# Sheet1.net
KiCad netlist of a schematic drawn in Altium Designer
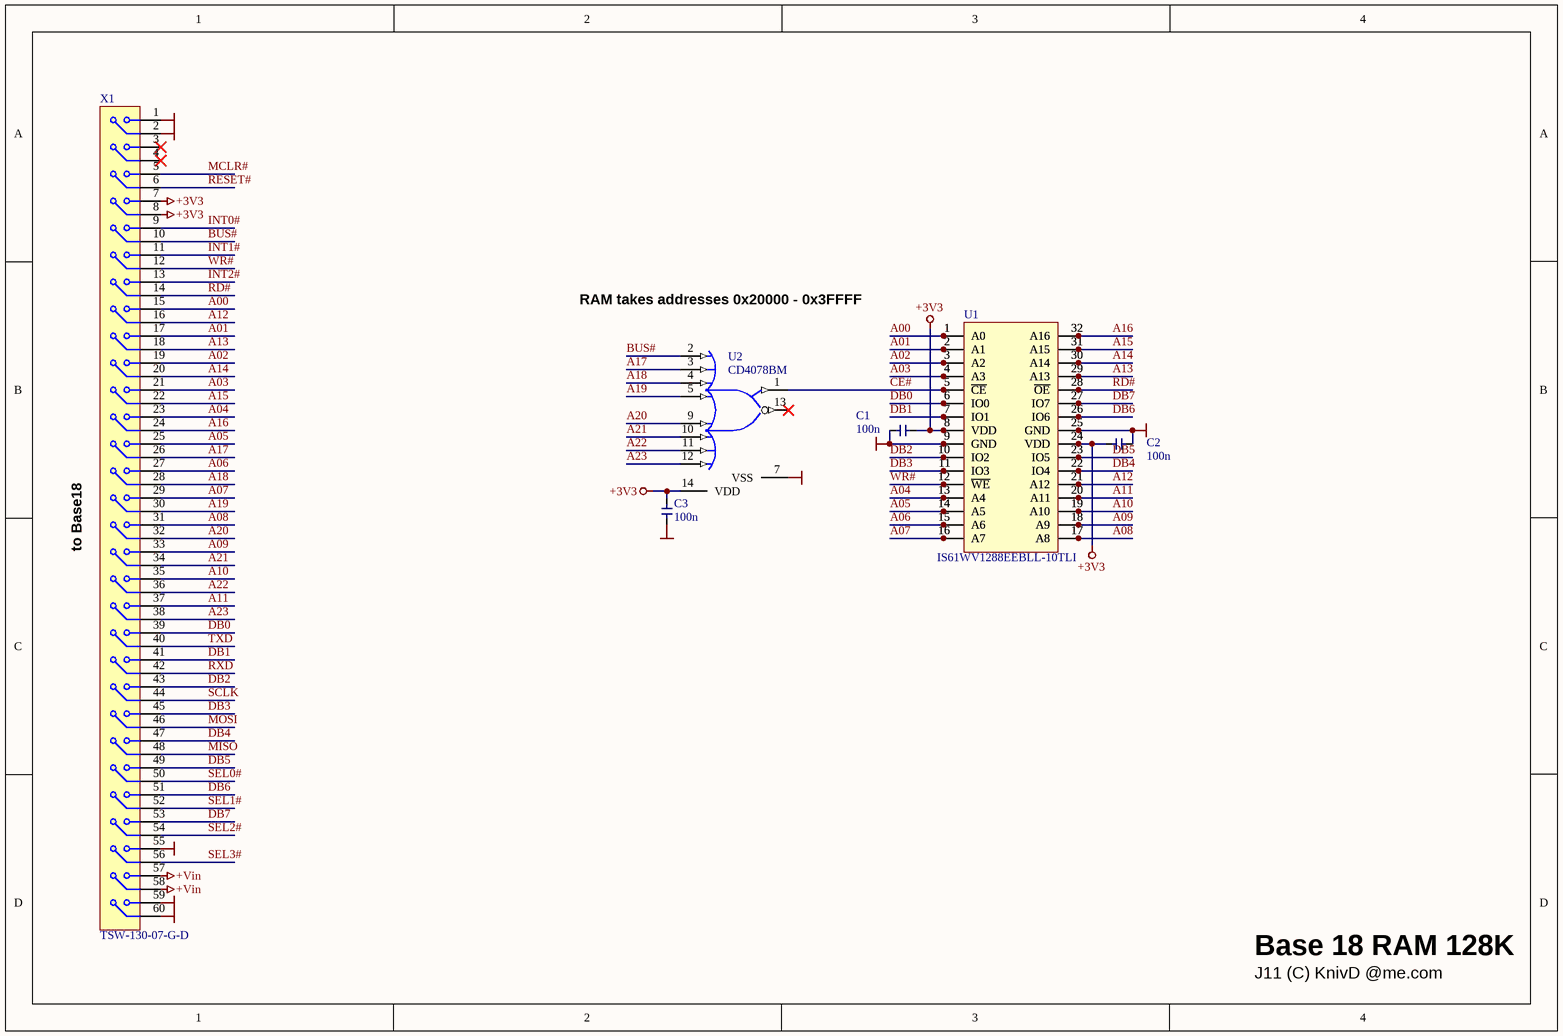
[diagram p0: Sheet1.SchDoc]

(export (version "E")
  (design (tool "Eeschema 10.0.6"))
  (components
    (comp (ref "C1")
      (value "100n")
      (footprint "CAPC3216X110N")
      (description "Capacitor")
      (libsource (lib "Discretes") (part "Capacitor"))
    )
    (comp (ref "C2")
      (value "100n")
      (footprint "CAPC3216X110N")
      (description "Capacitor")
      (libsource (lib "Discretes") (part "Capacitor"))
    )
    (comp (ref "C3")
      (value "100n")
      (footprint "CAPC3216X110N")
      (description "Capacitor")
      (libsource (lib "Discretes") (part "Capacitor"))
    )
    (comp (ref "U1")
      (value "IS61WV1288EEBLL-10TLI")
      (footprint "SOIC127P1413X280-32N")
      (description "128k x8 high-speed CMOS static RAM 3.3V")
      (fields (field (name "MANUFACTURER") "ISSI"))
      (libsource (lib "IC Other Functions") (part "IS63LV1024L"))
    )
    (comp (ref "U1A")
      (value "~")
      (footprint "SOJ127P1118X368-32N")
      (description "128k x8 high-speed CMOS static RAM 3.3V")
      (libsource (lib "IC Other Functions") (part "IS63LV1024L"))
    )
    (comp (ref "U2")
      (value "CD4078BM")
      (footprint "SOIC127P600X175-14N")
      (description "8-Input NOR Gate")
      (fields
        (field (name "PART NUMBER") "CD4078BE")
        (field (name "MANUFACTURER") "TEXAS INSTRUMENTS")
        (field (name "AUTHOR") "CERN DEM JLC")
      )
      (libsource (lib "ICs And Semiconductors") (part "4078"))
    )
    (comp (ref "X1")
      (value "TSW-130-07-G-D")
      (footprint "DIL60-M-EDGE")
      (description "Dual row, 60-way connector")
      (libsource (lib "Connectors") (part "Connector 2x30"))
    )
  )
  (nets
    (net (code "1") (name "+3V3") (class "Default")
      (node (ref "C1") (pin "1") (pintype "passive"))
      (node (ref "C2") (pin "1") (pintype "passive"))
      (node (ref "C3") (pin "1") (pintype "passive"))
      (node (ref "U1") (pin "24") (pinfunction "VDD_24") (pintype "passive"))
      (node (ref "U1") (pin "8") (pinfunction "VDD_8") (pintype "passive"))
      (node (ref "U1A") (pin "24") (pinfunction "VDD_24") (pintype "passive"))
      (node (ref "U1A") (pin "8") (pinfunction "VDD_8") (pintype "passive"))
      (node (ref "U2") (pin "14") (pinfunction "VDD_14") (pintype "power_in"))
      (node (ref "X1") (pin "7") (pinfunction "7_7") (pintype "passive"))
      (node (ref "X1") (pin "8") (pinfunction "8_8") (pintype "passive"))
    )
    (net (code "2") (name "+Vin") (class "Default")
      (node (ref "X1") (pin "57") (pinfunction "57_57") (pintype "passive"))
      (node (ref "X1") (pin "58") (pinfunction "58_58") (pintype "passive"))
    )
    (net (code "3") (name "/A00") (class "Default")
      (node (ref "U1") (pin "1") (pinfunction "A0_1") (pintype "passive"))
      (node (ref "U1A") (pin "1") (pinfunction "A0_1") (pintype "passive"))
      (node (ref "X1") (pin "15") (pinfunction "15_15") (pintype "passive"))
    )
    (net (code "4") (name "/A01") (class "Default")
      (node (ref "U1") (pin "2") (pinfunction "A1_2") (pintype "passive"))
      (node (ref "U1A") (pin "2") (pinfunction "A1_2") (pintype "passive"))
      (node (ref "X1") (pin "17") (pinfunction "17_17") (pintype "passive"))
    )
    (net (code "5") (name "/A02") (class "Default")
      (node (ref "U1") (pin "3") (pinfunction "A2_3") (pintype "passive"))
      (node (ref "U1A") (pin "3") (pinfunction "A2_3") (pintype "passive"))
      (node (ref "X1") (pin "19") (pinfunction "19_19") (pintype "passive"))
    )
    (net (code "6") (name "/A03") (class "Default")
      (node (ref "U1") (pin "4") (pinfunction "A3_4") (pintype "passive"))
      (node (ref "U1A") (pin "4") (pinfunction "A3_4") (pintype "passive"))
      (node (ref "X1") (pin "21") (pinfunction "21_21") (pintype "passive"))
    )
    (net (code "7") (name "/A04") (class "Default")
      (node (ref "U1") (pin "13") (pinfunction "A4_13") (pintype "passive"))
      (node (ref "U1A") (pin "13") (pinfunction "A4_13") (pintype "passive"))
      (node (ref "X1") (pin "23") (pinfunction "23_23") (pintype "passive"))
    )
    (net (code "8") (name "/A05") (class "Default")
      (node (ref "U1") (pin "14") (pinfunction "A5_14") (pintype "passive"))
      (node (ref "U1A") (pin "14") (pinfunction "A5_14") (pintype "passive"))
      (node (ref "X1") (pin "25") (pinfunction "25_25") (pintype "passive"))
    )
    (net (code "9") (name "/A06") (class "Default")
      (node (ref "U1") (pin "15") (pinfunction "A6_15") (pintype "passive"))
      (node (ref "U1A") (pin "15") (pinfunction "A6_15") (pintype "passive"))
      (node (ref "X1") (pin "27") (pinfunction "27_27") (pintype "passive"))
    )
    (net (code "10") (name "/A07") (class "Default")
      (node (ref "U1") (pin "16") (pinfunction "A7_16") (pintype "passive"))
      (node (ref "U1A") (pin "16") (pinfunction "A7_16") (pintype "passive"))
      (node (ref "X1") (pin "29") (pinfunction "29_29") (pintype "passive"))
    )
    (net (code "11") (name "/A08") (class "Default")
      (node (ref "U1") (pin "17") (pinfunction "A8_17") (pintype "passive"))
      (node (ref "U1A") (pin "17") (pinfunction "A8_17") (pintype "passive"))
      (node (ref "X1") (pin "31") (pinfunction "31_31") (pintype "passive"))
    )
    (net (code "12") (name "/A09") (class "Default")
      (node (ref "U1") (pin "18") (pinfunction "A9_18") (pintype "passive"))
      (node (ref "U1A") (pin "18") (pinfunction "A9_18") (pintype "passive"))
      (node (ref "X1") (pin "33") (pinfunction "33_33") (pintype "passive"))
    )
    (net (code "13") (name "/A10") (class "Default")
      (node (ref "U1") (pin "19") (pinfunction "A10_19") (pintype "passive"))
      (node (ref "U1A") (pin "19") (pinfunction "A10_19") (pintype "passive"))
      (node (ref "X1") (pin "35") (pinfunction "35_35") (pintype "passive"))
    )
    (net (code "14") (name "/A11") (class "Default")
      (node (ref "U1") (pin "20") (pinfunction "A11_20") (pintype "passive"))
      (node (ref "U1A") (pin "20") (pinfunction "A11_20") (pintype "passive"))
      (node (ref "X1") (pin "37") (pinfunction "37_37") (pintype "passive"))
    )
    (net (code "15") (name "/A12") (class "Default")
      (node (ref "U1") (pin "21") (pinfunction "A12_21") (pintype "passive"))
      (node (ref "U1A") (pin "21") (pinfunction "A12_21") (pintype "passive"))
      (node (ref "X1") (pin "16") (pinfunction "16_16") (pintype "passive"))
    )
    (net (code "16") (name "/A13") (class "Default")
      (node (ref "U1") (pin "29") (pinfunction "A13_29") (pintype "passive"))
      (node (ref "U1A") (pin "29") (pinfunction "A13_29") (pintype "passive"))
      (node (ref "X1") (pin "18") (pinfunction "18_18") (pintype "passive"))
    )
    (net (code "17") (name "/A14") (class "Default")
      (node (ref "U1") (pin "30") (pinfunction "A14_30") (pintype "passive"))
      (node (ref "U1A") (pin "30") (pinfunction "A14_30") (pintype "passive"))
      (node (ref "X1") (pin "20") (pinfunction "20_20") (pintype "passive"))
    )
    (net (code "18") (name "/A15") (class "Default")
      (node (ref "U1") (pin "31") (pinfunction "A15_31") (pintype "passive"))
      (node (ref "U1A") (pin "31") (pinfunction "A15_31") (pintype "passive"))
      (node (ref "X1") (pin "22") (pinfunction "22_22") (pintype "passive"))
    )
    (net (code "19") (name "/A16") (class "Default")
      (node (ref "U1") (pin "32") (pinfunction "A16_32") (pintype "passive"))
      (node (ref "U1A") (pin "32") (pinfunction "A16_32") (pintype "passive"))
      (node (ref "X1") (pin "24") (pinfunction "24_24") (pintype "passive"))
    )
    (net (code "20") (name "/A17") (class "Default")
      (node (ref "U2") (pin "3") (pintype "input"))
      (node (ref "X1") (pin "26") (pinfunction "26_26") (pintype "passive"))
    )
    (net (code "21") (name "/A18") (class "Default")
      (node (ref "U2") (pin "4") (pintype "input"))
      (node (ref "X1") (pin "28") (pinfunction "28_28") (pintype "passive"))
    )
    (net (code "22") (name "/A19") (class "Default")
      (node (ref "U2") (pin "5") (pintype "input"))
      (node (ref "X1") (pin "30") (pinfunction "30_30") (pintype "passive"))
    )
    (net (code "23") (name "/A20") (class "Default")
      (node (ref "U2") (pin "9") (pintype "input"))
      (node (ref "X1") (pin "32") (pinfunction "32_32") (pintype "passive"))
    )
    (net (code "24") (name "/A21") (class "Default")
      (node (ref "U2") (pin "10") (pintype "input"))
      (node (ref "X1") (pin "34") (pinfunction "34_34") (pintype "passive"))
    )
    (net (code "25") (name "/A22") (class "Default")
      (node (ref "U2") (pin "11") (pintype "input"))
      (node (ref "X1") (pin "36") (pinfunction "36_36") (pintype "passive"))
    )
    (net (code "26") (name "/A23") (class "Default")
      (node (ref "U2") (pin "12") (pintype "input"))
      (node (ref "X1") (pin "38") (pinfunction "38_38") (pintype "passive"))
    )
    (net (code "27") (name "/BUS#") (class "Default")
      (node (ref "U2") (pin "2") (pintype "input"))
      (node (ref "X1") (pin "10") (pinfunction "10_10") (pintype "passive"))
    )
    (net (code "28") (name "/CE#") (class "Default")
      (node (ref "U1") (pin "5") (pinfunction "~{CE}_5") (pintype "passive"))
      (node (ref "U1A") (pin "5") (pinfunction "~{CE}_5") (pintype "passive"))
      (node (ref "U2") (pin "1") (pintype "output"))
    )
    (net (code "29") (name "/DB0") (class "Default")
      (node (ref "U1") (pin "6") (pinfunction "IO0_6") (pintype "passive"))
      (node (ref "U1A") (pin "6") (pinfunction "IO0_6") (pintype "passive"))
      (node (ref "X1") (pin "39") (pinfunction "39_39") (pintype "passive"))
    )
    (net (code "30") (name "/DB1") (class "Default")
      (node (ref "U1") (pin "7") (pinfunction "IO1_7") (pintype "passive"))
      (node (ref "U1A") (pin "7") (pinfunction "IO1_7") (pintype "passive"))
      (node (ref "X1") (pin "41") (pinfunction "41_41") (pintype "passive"))
    )
    (net (code "31") (name "/DB2") (class "Default")
      (node (ref "U1") (pin "10") (pinfunction "IO2_10") (pintype "passive"))
      (node (ref "U1A") (pin "10") (pinfunction "IO2_10") (pintype "passive"))
      (node (ref "X1") (pin "43") (pinfunction "43_43") (pintype "passive"))
    )
    (net (code "32") (name "/DB3") (class "Default")
      (node (ref "U1") (pin "11") (pinfunction "IO3_11") (pintype "passive"))
      (node (ref "U1A") (pin "11") (pinfunction "IO3_11") (pintype "passive"))
      (node (ref "X1") (pin "45") (pinfunction "45_45") (pintype "passive"))
    )
    (net (code "33") (name "/DB4") (class "Default")
      (node (ref "U1") (pin "22") (pinfunction "IO4_22") (pintype "passive"))
      (node (ref "U1A") (pin "22") (pinfunction "IO4_22") (pintype "passive"))
      (node (ref "X1") (pin "47") (pinfunction "47_47") (pintype "passive"))
    )
    (net (code "34") (name "/DB5") (class "Default")
      (node (ref "U1") (pin "23") (pinfunction "IO5_23") (pintype "passive"))
      (node (ref "U1A") (pin "23") (pinfunction "IO5_23") (pintype "passive"))
      (node (ref "X1") (pin "49") (pinfunction "49_49") (pintype "passive"))
    )
    (net (code "35") (name "/DB6") (class "Default")
      (node (ref "U1") (pin "26") (pinfunction "IO6_26") (pintype "passive"))
      (node (ref "U1A") (pin "26") (pinfunction "IO6_26") (pintype "passive"))
      (node (ref "X1") (pin "51") (pinfunction "51_51") (pintype "passive"))
    )
    (net (code "36") (name "/DB7") (class "Default")
      (node (ref "U1") (pin "27") (pinfunction "IO7_27") (pintype "passive"))
      (node (ref "U1A") (pin "27") (pinfunction "IO7_27") (pintype "passive"))
      (node (ref "X1") (pin "53") (pinfunction "53_53") (pintype "passive"))
    )
    (net (code "37") (name "/INT0#") (class "Default")
      (node (ref "X1") (pin "9") (pinfunction "9_9") (pintype "passive"))
    )
    (net (code "38") (name "/INT1#") (class "Default")
      (node (ref "X1") (pin "11") (pinfunction "11_11") (pintype "passive"))
    )
    (net (code "39") (name "/INT2#") (class "Default")
      (node (ref "X1") (pin "13") (pinfunction "13_13") (pintype "passive"))
    )
    (net (code "40") (name "/MCLR#") (class "Default")
      (node (ref "X1") (pin "5") (pinfunction "5_5") (pintype "passive"))
    )
    (net (code "41") (name "/MISO") (class "Default")
      (node (ref "X1") (pin "48") (pinfunction "48_48") (pintype "passive"))
    )
    (net (code "42") (name "/MOSI") (class "Default")
      (node (ref "X1") (pin "46") (pinfunction "46_46") (pintype "passive"))
    )
    (net (code "43") (name "/RD#") (class "Default")
      (node (ref "U1") (pin "28") (pinfunction "~{OE}_28") (pintype "passive"))
      (node (ref "U1A") (pin "28") (pinfunction "~{OE}_28") (pintype "passive"))
      (node (ref "X1") (pin "14") (pinfunction "14_14") (pintype "passive"))
    )
    (net (code "44") (name "/RESET#") (class "Default")
      (node (ref "X1") (pin "6") (pinfunction "6_6") (pintype "passive"))
    )
    (net (code "45") (name "/RXD") (class "Default")
      (node (ref "X1") (pin "42") (pinfunction "42_42") (pintype "passive"))
    )
    (net (code "46") (name "/SCLK") (class "Default")
      (node (ref "X1") (pin "44") (pinfunction "44_44") (pintype "passive"))
    )
    (net (code "47") (name "/SEL0#") (class "Default")
      (node (ref "X1") (pin "50") (pinfunction "50_50") (pintype "passive"))
    )
    (net (code "48") (name "/SEL1#") (class "Default")
      (node (ref "X1") (pin "52") (pinfunction "52_52") (pintype "passive"))
    )
    (net (code "49") (name "/SEL2#") (class "Default")
      (node (ref "X1") (pin "54") (pinfunction "54_54") (pintype "passive"))
    )
    (net (code "50") (name "/SEL3#") (class "Default")
      (node (ref "X1") (pin "56") (pinfunction "56_56") (pintype "passive"))
    )
    (net (code "51") (name "/TXD") (class "Default")
      (node (ref "X1") (pin "40") (pinfunction "40_40") (pintype "passive"))
    )
    (net (code "52") (name "/WR#") (class "Default")
      (node (ref "U1") (pin "12") (pinfunction "~{WE}_12") (pintype "passive"))
      (node (ref "U1A") (pin "12") (pinfunction "~{WE}_12") (pintype "passive"))
      (node (ref "X1") (pin "12") (pinfunction "12_12") (pintype "passive"))
    )
    (net (code "53") (name "GND") (class "Default")
      (node (ref "C1") (pin "2") (pintype "passive"))
      (node (ref "C2") (pin "2") (pintype "passive"))
      (node (ref "C3") (pin "2") (pintype "passive"))
      (node (ref "U1") (pin "25") (pinfunction "GND_25") (pintype "passive"))
      (node (ref "U1") (pin "9") (pinfunction "GND_9") (pintype "passive"))
      (node (ref "U1A") (pin "25") (pinfunction "GND_25") (pintype "passive"))
      (node (ref "U1A") (pin "9") (pinfunction "GND_9") (pintype "passive"))
      (node (ref "U2") (pin "7") (pinfunction "VSS_7") (pintype "power_in"))
      (node (ref "X1") (pin "1") (pinfunction "1_1") (pintype "passive"))
      (node (ref "X1") (pin "2") (pinfunction "2_2") (pintype "passive"))
      (node (ref "X1") (pin "55") (pinfunction "55_55") (pintype "passive"))
      (node (ref "X1") (pin "59") (pinfunction "59_59") (pintype "passive"))
      (node (ref "X1") (pin "60") (pinfunction "60_60") (pintype "passive"))
    )
    (net (code "54") (name "unconnected-(U2-Pad13)") (class "Default")
      (node (ref "U2") (pin "13") (pintype "output+no_connect"))
    )
    (net (code "55") (name "unconnected-(X1-Pad3)") (class "Default")
      (node (ref "X1") (pin "3") (pinfunction "3_3") (pintype "passive+no_connect"))
    )
    (net (code "56") (name "unconnected-(X1-Pad4)") (class "Default")
      (node (ref "X1") (pin "4") (pinfunction "4_4") (pintype "passive+no_connect"))
    )
  )
)
